# IsoInput.net
KiCad netlist of a schematic drawn in Altium Designer
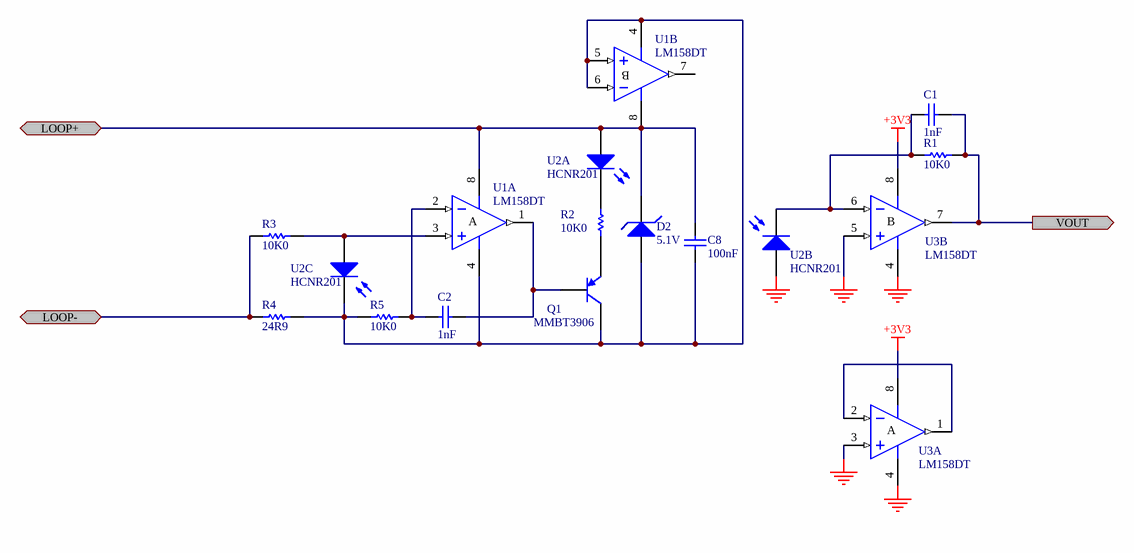
[diagram p0: IsoInput.SchDoc]

(export (version "E")
  (design (tool "Eeschema 10.0.6"))
  (components
    (comp (ref "C1")
      (value "1nF")
      (footprint "CAPC0805(2012)100_L")
      (description "CAP 1nF 50V ±10% 0805 (2012 Metric) Thickness 1mm SMD")
      (fields (field (name "TOLERANCE") "±10%"))
      (libsource (lib "Altium Content Vault") (part "CMP-1036-02980-1"))
    )
    (comp (ref "C2")
      (value "1nF")
      (footprint "CAPC0805(2012)100_L")
      (description "CAP 1nF 50V ±10% 0805 (2012 Metric) Thickness 1mm SMD")
      (fields (field (name "TOLERANCE") "±10%"))
      (libsource (lib "Altium Content Vault") (part "CMP-1036-02980-1"))
    )
    (comp (ref "C8")
      (value "100nF")
      (footprint "CAPC0805(2012)100_L")
      (description "CAP 100nF 50V ±10% 0805 (2012 Metric) Thickness 1mm SMD")
      (fields (field (name "TOLERANCE") "±10%"))
      (libsource (lib "Altium Content Vault") (part "CMP-1036-04420-1"))
    )
    (comp (ref "D2")
      (value "5.1V")
      (footprint "DIOD-S1M-13-F-SMA-2_V")
      (description "Surface Mount Glass Passivated Rectifier, 1000V, 1 A, -65 to 5.1V Zener Diode SMA")
      (fields (field (name "MANUFACTURER") "Diodes Inc") (field (name "PARTNUMBER") "S1M-13-F"))
      (libsource (lib "Altium Content Vault") (part "CMP-0639-00001-1"))
    )
    (comp (ref "Q1")
      (value "MMBT3906")
      (footprint "SOT23_N")
      (description "PNP Switching Transistor")
      (fields (field (name "PUBLISHER") "Altium Limited"))
      (libsource (lib "Philips Discrete BJT - Low Power") (part "MMBT3906"))
    )
    (comp (ref "R1")
      (value "10K0")
      (footprint "RESC0805(2012)_L")
      (description "10K 0.125W 1% 0805 (2012 Metric)  SMD")
      (fields (field (name "TOLERANCE") "1 %") (field (name "POWER") "0.125 W"))
      (libsource (lib "Altium Content Vault") (part "CMP-1013-00623-1"))
    )
    (comp (ref "R2")
      (value "10K0")
      (footprint "RESC0805(2012)_L")
      (description "10K 0.125W 1% 0805 (2012 Metric)  SMD")
      (fields (field (name "TOLERANCE") "1 %") (field (name "POWER") "0.125 W"))
      (libsource (lib "Altium Content Vault") (part "CMP-1013-00623-1"))
    )
    (comp (ref "R3")
      (value "10K0")
      (footprint "RESC0805(2012)_L")
      (description "10K 0.125W 1% 0805 (2012 Metric)  SMD")
      (fields (field (name "TOLERANCE") "1 %") (field (name "POWER") "0.125 W"))
      (libsource (lib "Altium Content Vault") (part "CMP-1013-00623-1"))
    )
    (comp (ref "R4")
      (value "24R9")
      (footprint "RESC0805(2012)_L")
      (description "24R9 0.125W 1% 0805 (2012 Metric)  SMD")
      (fields (field (name "POWER") "0.125 W") (field (name "TOLERANCE") "1 %"))
      (libsource (lib "Altium Content Vault") (part "CMP-1013-00327-1"))
    )
    (comp (ref "R5")
      (value "10K0")
      (footprint "RESC0805(2012)_L")
      (description "10K 0.125W 1% 0805 (2012 Metric)  SMD")
      (fields (field (name "TOLERANCE") "1 %") (field (name "POWER") "0.125 W"))
      (libsource (lib "Altium Content Vault") (part "CMP-1013-00623-1"))
    )
    (comp (ref "U1")
      (value "LM158DT")
      (footprint "SO8_N")
      (description "Low-Power Dual Operational Amplifier")
      (fields (field (name "PUBLISHER") "Altium Limited"))
      (libsource (lib "ST Operational Amplifier") (part "LM158AD"))
    )
    (comp (ref "U2")
      (value "HCNR201")
      (footprint "DIP-8W")
      (description "Analog Optocoupler")
      (libsource (lib "Agilent Optoelectronic LED") (part "HCNR201"))
    )
    (comp (ref "U3")
      (value "LM158DT")
      (footprint "SO8_N")
      (description "Low-Power Dual Operational Amplifier")
      (fields (field (name "PUBLISHER") "Altium Limited"))
      (libsource (lib "ST Operational Amplifier") (part "LM158AD"))
    )
  )
  (nets
    (net (code "1") (name "+3V3") (class "Default")
      (node (ref "U3") (pin "8") (pinfunction "V+_8") (pintype "power_in"))
    )
    (net (code "2") (name "/LOOP+") (class "Default")
      (node (ref "C8") (pin "2") (pinfunction "2_2") (pintype "passive"))
      (node (ref "D2") (pin "2") (pinfunction "K_2") (pintype "passive"))
      (node (ref "U1") (pin "8") (pinfunction "V+_8") (pintype "power_in"))
      (node (ref "U2") (pin "2") (pinfunction "A_2") (pintype "passive"))
    )
    (net (code "3") (name "/LOOP-") (class "Default")
      (node (ref "R3") (pin "2") (pinfunction "2_2") (pintype "passive"))
      (node (ref "R4") (pin "1") (pinfunction "1_1") (pintype "passive"))
    )
    (net (code "4") (name "/VOUT") (class "Default")
      (node (ref "C1") (pin "2") (pinfunction "2_2") (pintype "passive"))
      (node (ref "R1") (pin "1") (pinfunction "1_1") (pintype "passive"))
      (node (ref "U3") (pin "7") (pinfunction "OUT_7") (pintype "output"))
    )
    (net (code "5") (name "GND") (class "Default")
      (node (ref "U2") (pin "4") (pinfunction "PD1A_4") (pintype "passive"))
      (node (ref "U3") (pin "3") (pinfunction "IN+_3") (pintype "input"))
      (node (ref "U3") (pin "4") (pinfunction "V-_4") (pintype "power_in"))
      (node (ref "U3") (pin "5") (pinfunction "IN+_5") (pintype "input"))
    )
    (net (code "6") (name "Net-(D2-A)") (class "Default")
      (node (ref "C8") (pin "1") (pinfunction "1_1") (pintype "passive"))
      (node (ref "D2") (pin "1") (pinfunction "A_1") (pintype "passive"))
      (node (ref "Q1") (pin "3") (pinfunction "C_3") (pintype "passive"))
      (node (ref "R4") (pin "2") (pinfunction "2_2") (pintype "passive"))
      (node (ref "R5") (pin "2") (pinfunction "2_2") (pintype "passive"))
      (node (ref "U1") (pin "4") (pinfunction "V-_4") (pintype "power_in"))
      (node (ref "U1") (pin "5") (pinfunction "IN+_5") (pintype "input"))
      (node (ref "U1") (pin "6") (pinfunction "IN-_6") (pintype "input"))
      (node (ref "U2") (pin "6") (pinfunction "PD2K_6") (pintype "passive"))
    )
    (net (code "7") (name "Net-(Q1-B)") (class "Default")
      (node (ref "C2") (pin "2") (pinfunction "2_2") (pintype "passive"))
      (node (ref "Q1") (pin "1") (pinfunction "B_1") (pintype "passive"))
      (node (ref "U1") (pin "1") (pinfunction "OUT_1") (pintype "output"))
    )
    (net (code "8") (name "Net-(Q1-E)") (class "Default")
      (node (ref "Q1") (pin "2") (pinfunction "E_2") (pintype "passive"))
      (node (ref "R2") (pin "1") (pinfunction "1_1") (pintype "passive"))
    )
    (net (code "9") (name "Net-(U1A-IN+)") (class "Default")
      (node (ref "R3") (pin "1") (pinfunction "1_1") (pintype "passive"))
      (node (ref "U1") (pin "3") (pinfunction "IN+_3") (pintype "input"))
      (node (ref "U2") (pin "5") (pinfunction "PD2A_5") (pintype "passive"))
    )
    (net (code "10") (name "Net-(U1A-IN-)") (class "Default")
      (node (ref "C2") (pin "1") (pinfunction "1_1") (pintype "passive"))
      (node (ref "R5") (pin "1") (pinfunction "1_1") (pintype "passive"))
      (node (ref "U1") (pin "2") (pinfunction "IN-_2") (pintype "input"))
    )
    (net (code "11") (name "Net-(U2A-K)") (class "Default")
      (node (ref "R2") (pin "2") (pinfunction "2_2") (pintype "passive"))
      (node (ref "U2") (pin "1") (pinfunction "K_1") (pintype "passive"))
    )
    (net (code "12") (name "Net-(U2B-PD1K)") (class "Default")
      (node (ref "C1") (pin "1") (pinfunction "1_1") (pintype "passive"))
      (node (ref "R1") (pin "2") (pinfunction "2_2") (pintype "passive"))
      (node (ref "U2") (pin "3") (pinfunction "PD1K_3") (pintype "passive"))
      (node (ref "U3") (pin "6") (pinfunction "IN-_6") (pintype "input"))
    )
    (net (code "13") (name "Net-(U3A-IN-)") (class "Default")
      (node (ref "U3") (pin "1") (pinfunction "OUT_1") (pintype "output"))
      (node (ref "U3") (pin "2") (pinfunction "IN-_2") (pintype "input"))
    )
    (net (code "14") (name "unconnected-(U1B-OUT-Pad7)") (class "Default")
      (node (ref "U1") (pin "7") (pinfunction "OUT_7") (pintype "output"))
    )
  )
)
